# d-ticker.net
KiCad netlist of a schematic drawn in EAGLE
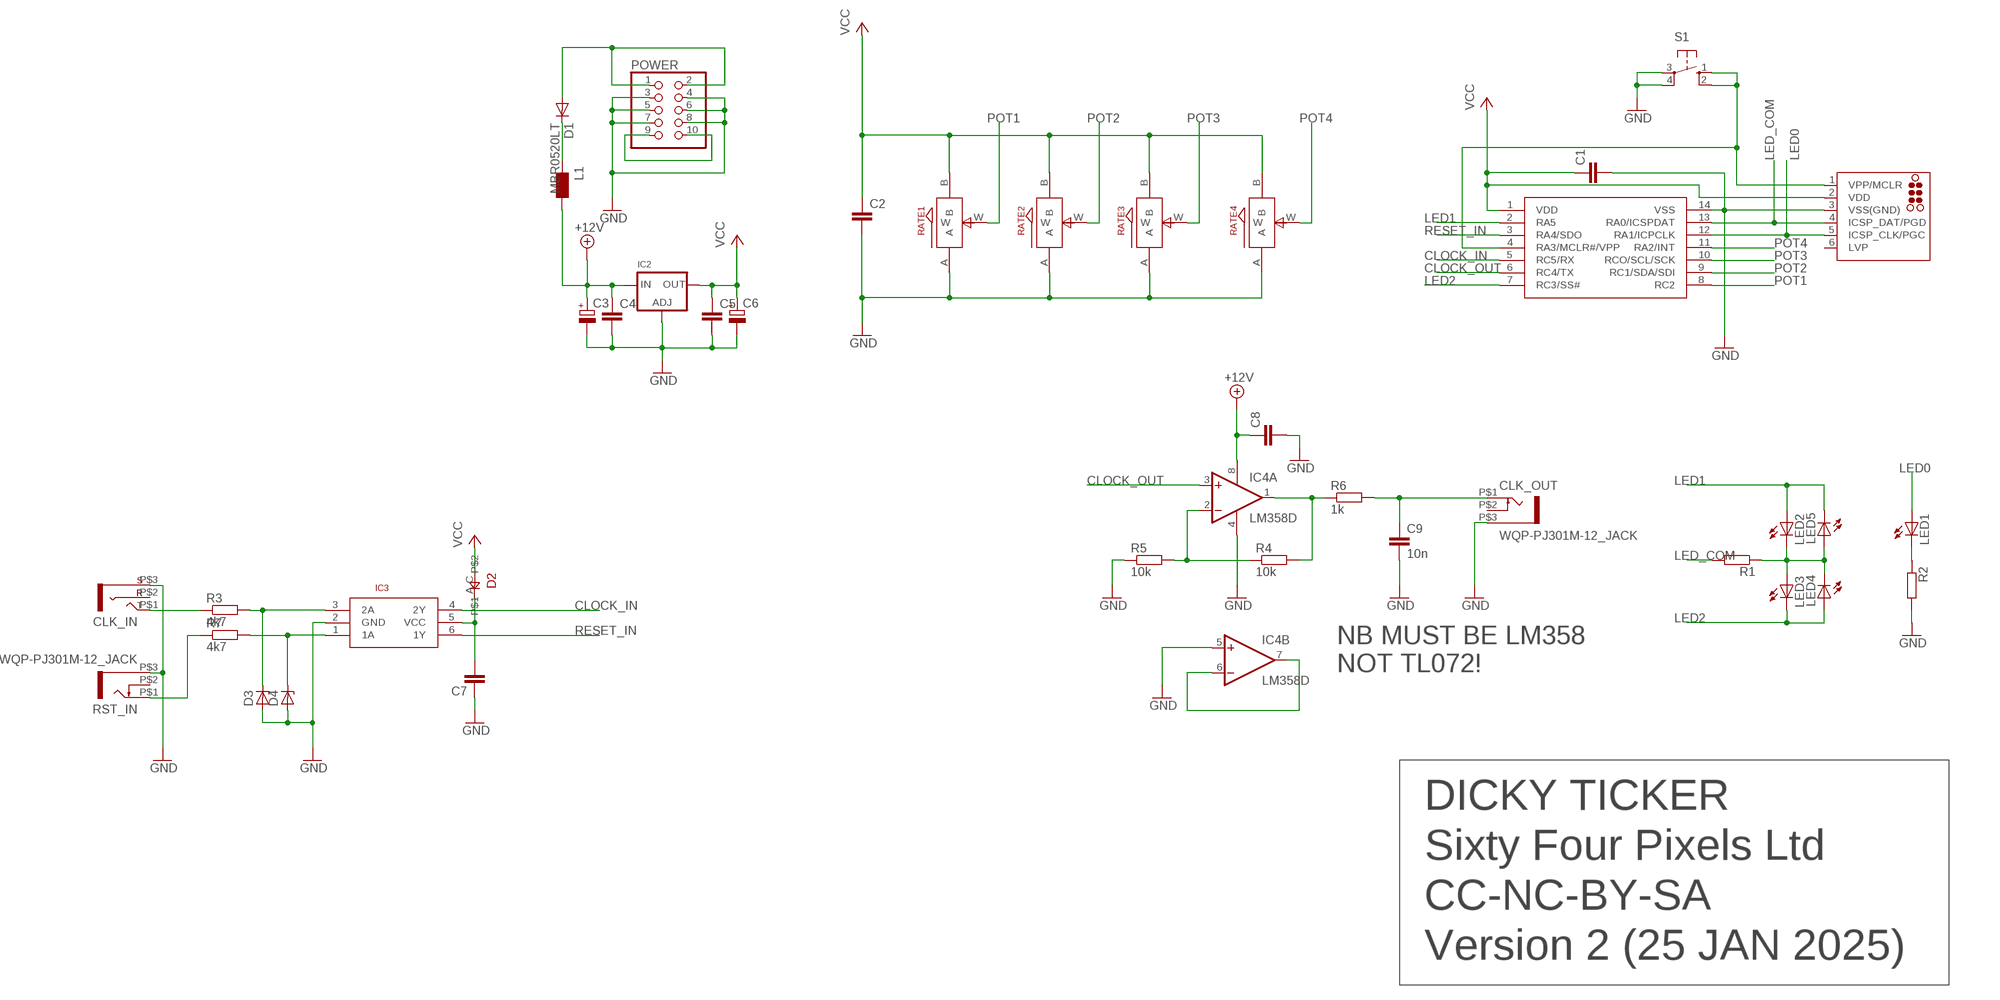
[diagram p0: schematic, sheet 1]

(export (version "E")
  (design (tool "Eeschema 10.0.6"))
  (components
    (comp (ref "C1")
      (value "C-EUC0805")
      (footprint "eagle-import:C0805")
      (libsource (lib "eagle-import") (part "C-EUC0805"))
    )
    (comp (ref "C2")
      (value "C-EUC0805")
      (footprint "eagle-import:C0805")
      (libsource (lib "eagle-import") (part "C-EUC0805"))
    )
    (comp (ref "C3")
      (value "CPOL-EUSMCA")
      (footprint "eagle-import:SMC_A")
      (libsource (lib "eagle-import") (part "CPOL-EUSMCA"))
    )
    (comp (ref "C4")
      (value "C-EUC0805")
      (footprint "eagle-import:C0805")
      (libsource (lib "eagle-import") (part "C-EUC0805"))
    )
    (comp (ref "C5")
      (value "C-EUC0805")
      (footprint "eagle-import:C0805")
      (libsource (lib "eagle-import") (part "C-EUC0805"))
    )
    (comp (ref "C6")
      (value "CPOL-EUSMCA")
      (footprint "eagle-import:SMC_A")
      (libsource (lib "eagle-import") (part "CPOL-EUSMCA"))
    )
    (comp (ref "C7")
      (value "C-EUC0805")
      (footprint "eagle-import:C0805")
      (libsource (lib "eagle-import") (part "C-EUC0805"))
    )
    (comp (ref "C8")
      (value "C-EUC0805")
      (footprint "eagle-import:C0805")
      (libsource (lib "eagle-import") (part "C-EUC0805"))
    )
    (comp (ref "C9")
      (value "10n")
      (footprint "eagle-import:C0805")
      (libsource (lib "eagle-import") (part "C-EUC0805"))
    )
    (comp (ref "CLK_IN")
      (value "THONKICONN_STEREO")
      (footprint "eagle-import:WQP-PJ301M-ST")
      (libsource (lib "eagle-import") (part "THONKICONN_STEREO"))
    )
    (comp (ref "CLK_OUT")
      (value "WQP-PJ301M-12_JACK")
      (footprint "eagle-import:WQP-PJ301M-12_JACK")
      (libsource (lib "eagle-import") (part "WQP-PJ301M-12_JACK"))
    )
    (comp (ref "D1")
      (value "MBR0520LT")
      (footprint "eagle-import:SOD123")
      (libsource (lib "eagle-import") (part "MBR0520LT"))
    )
    (comp (ref "D2")
      (value "0805DIODE")
      (footprint "eagle-import:0805DIODE")
      (libsource (lib "eagle-import") (part "0805DIODE"))
    )
    (comp (ref "D3")
      (value "ZENER-DIODESOD80C")
      (footprint "eagle-import:SOD80C")
      (libsource (lib "eagle-import") (part "ZENER-DIODESOD80C"))
    )
    (comp (ref "D4")
      (value "ZENER-DIODESOD80C")
      (footprint "eagle-import:SOD80C")
      (libsource (lib "eagle-import") (part "ZENER-DIODESOD80C"))
    )
    (comp (ref "IC1")
      (value "PIC16F1825SO14")
      (footprint "eagle-import:SO14")
      (libsource (lib "eagle-import") (part "PIC16F1825SO14"))
    )
    (comp (ref "IC2")
      (value "LM1117SOT223-WAVE")
      (footprint "eagle-import:SOT223-W")
      (libsource (lib "eagle-import") (part "LM1117SOT223-WAVE"))
    )
    (comp (ref "IC3")
      (value "SN74LVC2G14")
      (footprint "eagle-import:DBV_R-PDSO-G6")
      (libsource (lib "eagle-import") (part "SN74LVC2G14"))
    )
    (comp (ref "IC4")
      (value "LM358D")
      (footprint "eagle-import:SO08")
      (libsource (lib "eagle-import") (part "LM358D"))
    )
    (comp (ref "ICSP")
      (value "TC2030-MCP-NL")
      (footprint "eagle-import:TC2030-MCP-NL")
      (libsource (lib "eagle-import") (part "TC2030-MCP-NL"))
    )
    (comp (ref "L1")
      (value "WE-CBF_0805")
      (footprint "eagle-import:0805")
      (libsource (lib "eagle-import") (part "WE-CBF_0805"))
    )
    (comp (ref "LED1")
      (value "LED3MM")
      (footprint "eagle-import:LED3MM")
      (libsource (lib "eagle-import") (part "LED3MM"))
    )
    (comp (ref "LED2")
      (value "LED3MM")
      (footprint "eagle-import:LED3MM")
      (libsource (lib "eagle-import") (part "LED3MM"))
    )
    (comp (ref "LED3")
      (value "LED3MM")
      (footprint "eagle-import:LED3MM")
      (libsource (lib "eagle-import") (part "LED3MM"))
    )
    (comp (ref "LED4")
      (value "LED3MM")
      (footprint "eagle-import:LED3MM")
      (libsource (lib "eagle-import") (part "LED3MM"))
    )
    (comp (ref "LED5")
      (value "LED3MM")
      (footprint "eagle-import:LED3MM")
      (libsource (lib "eagle-import") (part "LED3MM"))
    )
    (comp (ref "POWER")
      (value "PINHD-2X5")
      (footprint "eagle-import:2X05")
      (libsource (lib "eagle-import") (part "PINHD-2X5"))
    )
    (comp (ref "R1")
      (value "R-EU_R0805")
      (footprint "eagle-import:R0805")
      (libsource (lib "eagle-import") (part "R-EU_R0805"))
    )
    (comp (ref "R2")
      (value "R-EU_R0805")
      (footprint "eagle-import:R0805")
      (libsource (lib "eagle-import") (part "R-EU_R0805"))
    )
    (comp (ref "R3")
      (value "4k7")
      (footprint "eagle-import:R0805")
      (libsource (lib "eagle-import") (part "R-EU_R0805"))
    )
    (comp (ref "R4")
      (value "10k")
      (footprint "eagle-import:R0805")
      (libsource (lib "eagle-import") (part "R-EU_R0805"))
    )
    (comp (ref "R5")
      (value "10k")
      (footprint "eagle-import:R0805")
      (libsource (lib "eagle-import") (part "R-EU_R0805"))
    )
    (comp (ref "R6")
      (value "1k")
      (footprint "eagle-import:R0805")
      (libsource (lib "eagle-import") (part "R-EU_R0805"))
    )
    (comp (ref "R7")
      (value "4k7")
      (footprint "eagle-import:R0805")
      (libsource (lib "eagle-import") (part "R-EU_R0805"))
    )
    (comp (ref "RATE1")
      (value "ALPS_POT_SMALL")
      (footprint "eagle-import:SMALL_ALPS_POT")
      (libsource (lib "eagle-import") (part "ALPS_POT_SMALL"))
    )
    (comp (ref "RATE2")
      (value "ALPS_POT_SMALL")
      (footprint "eagle-import:SMALL_ALPS_POT")
      (libsource (lib "eagle-import") (part "ALPS_POT_SMALL"))
    )
    (comp (ref "RATE3")
      (value "ALPS_POT_SMALL")
      (footprint "eagle-import:SMALL_ALPS_POT")
      (libsource (lib "eagle-import") (part "ALPS_POT_SMALL"))
    )
    (comp (ref "RATE4")
      (value "ALPS_POT_SMALL")
      (footprint "eagle-import:SMALL_ALPS_POT")
      (libsource (lib "eagle-import") (part "ALPS_POT_SMALL"))
    )
    (comp (ref "RST_IN")
      (value "WQP-PJ301M-12_JACK")
      (footprint "eagle-import:WQP-PJ301M-12_JACK")
      (libsource (lib "eagle-import") (part "WQP-PJ301M-12_JACK"))
    )
    (comp (ref "S1")
      (value "10-XX")
      (footprint "eagle-import:B3F-10XX")
      (fields (field (name "MPN") "B3F-1000"))
      (libsource (lib "eagle-import") (part "10-XX"))
    )
  )
  (nets
    (net (code "1") (name "+12V") (class "Default")
      (node (ref "C3") (pin "+") (pinfunction "+_+") (pintype "passive"))
      (node (ref "C4") (pin "1") (pinfunction "1_1") (pintype "passive"))
      (node (ref "C8") (pin "1") (pinfunction "1_1") (pintype "passive"))
      (node (ref "IC2") (pin "3") (pinfunction "IN_3") (pintype "input"))
      (node (ref "IC4") (pin "8") (pinfunction "V+_8") (pintype "power_in"))
      (node (ref "L1") (pin "2") (pinfunction "2_2") (pintype "passive"))
    )
    (net (code "2") (name "/CLOCK_IN") (class "Default")
      (node (ref "IC1") (pin "5") (pinfunction "RC5/RX_5") (pintype "bidirectional"))
      (node (ref "IC3") (pin "4") (pinfunction "2Y_4") (pintype "output"))
    )
    (net (code "3") (name "/CLOCK_OUT") (class "Default")
      (node (ref "IC1") (pin "6") (pinfunction "RC4/TX_6") (pintype "bidirectional"))
      (node (ref "IC4") (pin "3") (pinfunction "+IN_3") (pintype "input"))
    )
    (net (code "4") (name "/LED0") (class "Default")
      (node (ref "IC1") (pin "12") (pinfunction "RA1/ICPCLK_12") (pintype "bidirectional"))
      (node (ref "ICSP") (pin "5") (pinfunction "ICSP_CLK/PGC_5") (pintype "output"))
      (node (ref "LED1") (pin "A") (pinfunction "A_A") (pintype "passive"))
    )
    (net (code "5") (name "/LED1") (class "Default")
      (node (ref "IC1") (pin "2") (pinfunction "RA5_2") (pintype "bidirectional"))
      (node (ref "LED2") (pin "A") (pinfunction "A_A") (pintype "passive"))
      (node (ref "LED5") (pin "K") (pinfunction "C_K") (pintype "passive"))
    )
    (net (code "6") (name "/LED2") (class "Default")
      (node (ref "IC1") (pin "7") (pinfunction "RC3/SS#_7") (pintype "bidirectional"))
      (node (ref "LED3") (pin "K") (pinfunction "C_K") (pintype "passive"))
      (node (ref "LED4") (pin "A") (pinfunction "A_A") (pintype "passive"))
    )
    (net (code "7") (name "/LED_COM") (class "Default")
      (node (ref "IC1") (pin "13") (pinfunction "RA0/ICSPDAT_13") (pintype "bidirectional"))
      (node (ref "ICSP") (pin "4") (pinfunction "ICSP_DAT/PGD_4") (pintype "bidirectional"))
      (node (ref "R1") (pin "2") (pinfunction "2_2") (pintype "passive"))
    )
    (net (code "8") (name "/POT1") (class "Default")
      (node (ref "IC1") (pin "8") (pinfunction "RC2_8") (pintype "bidirectional"))
      (node (ref "RATE1") (pin "W") (pinfunction "W_W") (pintype "bidirectional"))
    )
    (net (code "9") (name "/POT2") (class "Default")
      (node (ref "IC1") (pin "9") (pinfunction "RC1/SDA/SDI_9") (pintype "bidirectional"))
      (node (ref "RATE2") (pin "W") (pinfunction "W_W") (pintype "bidirectional"))
    )
    (net (code "10") (name "/POT3") (class "Default")
      (node (ref "IC1") (pin "10") (pinfunction "RCO/SCL/SCK_10") (pintype "bidirectional"))
      (node (ref "RATE3") (pin "W") (pinfunction "W_W") (pintype "bidirectional"))
    )
    (net (code "11") (name "/POT4") (class "Default")
      (node (ref "IC1") (pin "11") (pinfunction "RA2/INT_11") (pintype "bidirectional"))
      (node (ref "RATE4") (pin "W") (pinfunction "W_W") (pintype "bidirectional"))
    )
    (net (code "12") (name "/RESET_IN") (class "Default")
      (node (ref "IC1") (pin "3") (pinfunction "RA4/SDO_3") (pintype "bidirectional"))
      (node (ref "IC3") (pin "6") (pinfunction "1Y_6") (pintype "output"))
    )
    (net (code "13") (name "GND") (class "Default")
      (node (ref "C1") (pin "2") (pinfunction "2_2") (pintype "passive"))
      (node (ref "C2") (pin "2") (pinfunction "2_2") (pintype "passive"))
      (node (ref "C3") (pin "-") (pinfunction "-_-") (pintype "passive"))
      (node (ref "C4") (pin "2") (pinfunction "2_2") (pintype "passive"))
      (node (ref "C5") (pin "2") (pinfunction "2_2") (pintype "passive"))
      (node (ref "C6") (pin "-") (pinfunction "-_-") (pintype "passive"))
      (node (ref "C7") (pin "1") (pinfunction "1_1") (pintype "passive"))
      (node (ref "C8") (pin "2") (pinfunction "2_2") (pintype "passive"))
      (node (ref "C9") (pin "2") (pinfunction "2_2") (pintype "passive"))
      (node (ref "CLK_IN") (pin "P$3") (pinfunction "S_P$3") (pintype "passive"))
      (node (ref "CLK_OUT") (pin "P$3") (pinfunction "1_P$3") (pintype "passive"))
      (node (ref "D3") (pin "A") (pinfunction "A_A") (pintype "passive"))
      (node (ref "D4") (pin "A") (pinfunction "A_A") (pintype "passive"))
      (node (ref "IC1") (pin "14") (pinfunction "VSS_14") (pintype "power_in"))
      (node (ref "IC2") (pin "1") (pinfunction "ADJ_1") (pintype "input"))
      (node (ref "IC3") (pin "2") (pinfunction "GND_2") (pintype "power_in"))
      (node (ref "IC4") (pin "4") (pinfunction "V-_4") (pintype "power_in"))
      (node (ref "IC4") (pin "5") (pinfunction "+IN_5") (pintype "input"))
      (node (ref "ICSP") (pin "3") (pinfunction "VSS(GND)_3") (pintype "power_in"))
      (node (ref "POWER") (pin "3") (pinfunction "3_3") (pintype "passive"))
      (node (ref "POWER") (pin "4") (pinfunction "4_4") (pintype "passive"))
      (node (ref "POWER") (pin "5") (pinfunction "5_5") (pintype "passive"))
      (node (ref "POWER") (pin "6") (pinfunction "6_6") (pintype "passive"))
      (node (ref "POWER") (pin "7") (pinfunction "7_7") (pintype "passive"))
      (node (ref "POWER") (pin "8") (pinfunction "8_8") (pintype "passive"))
      (node (ref "R2") (pin "2") (pinfunction "2_2") (pintype "passive"))
      (node (ref "R5") (pin "1") (pinfunction "1_1") (pintype "passive"))
      (node (ref "RATE1") (pin "A") (pinfunction "A_A") (pintype "bidirectional"))
      (node (ref "RATE2") (pin "A") (pinfunction "A_A") (pintype "bidirectional"))
      (node (ref "RATE3") (pin "A") (pinfunction "A_A") (pintype "bidirectional"))
      (node (ref "RATE4") (pin "A") (pinfunction "A_A") (pintype "bidirectional"))
      (node (ref "RST_IN") (pin "P$3") (pinfunction "1_P$3") (pintype "passive"))
      (node (ref "S1") (pin "3") (pinfunction "P_3") (pintype "passive"))
      (node (ref "S1") (pin "4") (pinfunction "P1_4") (pintype "passive"))
    )
    (net (code "14") (name "Net-(CLK_IN-T)") (class "Default")
      (node (ref "CLK_IN") (pin "P$1") (pinfunction "T_P$1") (pintype "passive"))
      (node (ref "R3") (pin "1") (pinfunction "1_1") (pintype "passive"))
    )
    (net (code "15") (name "Net-(CLK_OUT-2)") (class "Default")
      (node (ref "C9") (pin "1") (pinfunction "1_1") (pintype "passive"))
      (node (ref "CLK_OUT") (pin "P$1") (pinfunction "2_P$1") (pintype "passive"))
      (node (ref "R6") (pin "2") (pinfunction "2_2") (pintype "passive"))
    )
    (net (code "16") (name "Net-(D1-PadA)") (class "Default")
      (node (ref "D1") (pin "A") (pinfunction "A_A") (pintype "passive"))
      (node (ref "POWER") (pin "1") (pinfunction "1_1") (pintype "passive"))
      (node (ref "POWER") (pin "2") (pinfunction "2_2") (pintype "passive"))
    )
    (net (code "17") (name "Net-(D1-PadC)") (class "Default")
      (node (ref "D1") (pin "C") (pinfunction "C_C") (pintype "passive"))
      (node (ref "L1") (pin "1") (pinfunction "1_1") (pintype "passive"))
    )
    (net (code "18") (name "Net-(D2-P$2)") (class "Default")
      (node (ref "C7") (pin "2") (pinfunction "2_2") (pintype "passive"))
      (node (ref "D2") (pin "A") (pinfunction "P$2_A") (pintype "bidirectional"))
      (node (ref "IC3") (pin "5") (pinfunction "VCC_5") (pintype "power_in"))
    )
    (net (code "19") (name "Net-(IC1-RA3{slash}MCLR#{slash}VPP)") (class "Default")
      (node (ref "IC1") (pin "4") (pinfunction "RA3/MCLR#/VPP_4") (pintype "input"))
      (node (ref "ICSP") (pin "1") (pinfunction "VPP/MCLR_1") (pintype "passive"))
      (node (ref "S1") (pin "1") (pinfunction "S_1") (pintype "passive"))
      (node (ref "S1") (pin "2") (pinfunction "S1_2") (pintype "passive"))
    )
    (net (code "20") (name "Net-(IC3-1A)") (class "Default")
      (node (ref "D4") (pin "C") (pinfunction "C_C") (pintype "passive"))
      (node (ref "IC3") (pin "1") (pinfunction "1A_1") (pintype "input"))
      (node (ref "R7") (pin "2") (pinfunction "2_2") (pintype "passive"))
    )
    (net (code "21") (name "Net-(IC3-2A)") (class "Default")
      (node (ref "D3") (pin "C") (pinfunction "C_C") (pintype "passive"))
      (node (ref "IC3") (pin "3") (pinfunction "2A_3") (pintype "input"))
      (node (ref "R3") (pin "2") (pinfunction "2_2") (pintype "passive"))
    )
    (net (code "22") (name "Net-(IC4A--IN)") (class "Default")
      (node (ref "IC4") (pin "2") (pinfunction "-IN_2") (pintype "input"))
      (node (ref "R4") (pin "1") (pinfunction "1_1") (pintype "passive"))
      (node (ref "R5") (pin "2") (pinfunction "2_2") (pintype "passive"))
    )
    (net (code "23") (name "Net-(IC4A-OUT)") (class "Default")
      (node (ref "IC4") (pin "1") (pinfunction "OUT_1") (pintype "output"))
      (node (ref "R4") (pin "2") (pinfunction "2_2") (pintype "passive"))
      (node (ref "R6") (pin "1") (pinfunction "1_1") (pintype "passive"))
    )
    (net (code "24") (name "Net-(IC4B--IN)") (class "Default")
      (node (ref "IC4") (pin "6") (pinfunction "-IN_6") (pintype "input"))
      (node (ref "IC4") (pin "7") (pinfunction "OUT_7") (pintype "output"))
    )
    (net (code "25") (name "Net-(LED1-C)") (class "Default")
      (node (ref "LED1") (pin "K") (pinfunction "C_K") (pintype "passive"))
      (node (ref "R2") (pin "1") (pinfunction "1_1") (pintype "passive"))
    )
    (net (code "26") (name "Net-(LED2-C)") (class "Default")
      (node (ref "LED2") (pin "K") (pinfunction "C_K") (pintype "passive"))
      (node (ref "LED3") (pin "A") (pinfunction "A_A") (pintype "passive"))
      (node (ref "LED4") (pin "K") (pinfunction "C_K") (pintype "passive"))
      (node (ref "LED5") (pin "A") (pinfunction "A_A") (pintype "passive"))
      (node (ref "R1") (pin "1") (pinfunction "1_1") (pintype "passive"))
    )
    (net (code "27") (name "Net-(POWER-Pad10)") (class "Default")
      (node (ref "POWER") (pin "10") (pinfunction "10_10") (pintype "passive"))
      (node (ref "POWER") (pin "9") (pinfunction "9_9") (pintype "passive"))
    )
    (net (code "28") (name "Net-(RST_IN-2)") (class "Default")
      (node (ref "R7") (pin "1") (pinfunction "1_1") (pintype "passive"))
      (node (ref "RST_IN") (pin "P$1") (pinfunction "2_P$1") (pintype "passive"))
    )
    (net (code "29") (name "VCC") (class "Default")
      (node (ref "C1") (pin "1") (pinfunction "1_1") (pintype "passive"))
      (node (ref "C2") (pin "1") (pinfunction "1_1") (pintype "passive"))
      (node (ref "C5") (pin "1") (pinfunction "1_1") (pintype "passive"))
      (node (ref "C6") (pin "+") (pinfunction "+_+") (pintype "passive"))
      (node (ref "D2") (pin "C") (pinfunction "P$1_C") (pintype "bidirectional"))
      (node (ref "IC1") (pin "1") (pinfunction "VDD_1") (pintype "power_in"))
      (node (ref "IC2") (pin "2") (pinfunction "OUT_2") (pintype "passive"))
      (node (ref "ICSP") (pin "2") (pinfunction "VDD_2") (pintype "power_in"))
      (node (ref "RATE1") (pin "B") (pinfunction "B_B") (pintype "bidirectional"))
      (node (ref "RATE2") (pin "B") (pinfunction "B_B") (pintype "bidirectional"))
      (node (ref "RATE3") (pin "B") (pinfunction "B_B") (pintype "bidirectional"))
      (node (ref "RATE4") (pin "B") (pinfunction "B_B") (pintype "bidirectional"))
    )
    (net (code "30") (name "unconnected-(CLK_IN-R-PadP$2)") (class "Default")
      (node (ref "CLK_IN") (pin "P$2") (pinfunction "R_P$2") (pintype "passive"))
    )
    (net (code "31") (name "unconnected-(CLK_OUT-3-PadP$2)") (class "Default")
      (node (ref "CLK_OUT") (pin "P$2") (pinfunction "3_P$2") (pintype "passive"))
    )
    (net (code "32") (name "unconnected-(ICSP-LVP-Pad6)") (class "Default")
      (node (ref "ICSP") (pin "6") (pinfunction "LVP_6") (pintype "bidirectional"))
    )
    (net (code "33") (name "unconnected-(RST_IN-3-PadP$2)") (class "Default")
      (node (ref "RST_IN") (pin "P$2") (pinfunction "3_P$2") (pintype "passive"))
    )
  )
)
